# OMAPProc.net
KiCad netlist of a schematic drawn in EAGLE
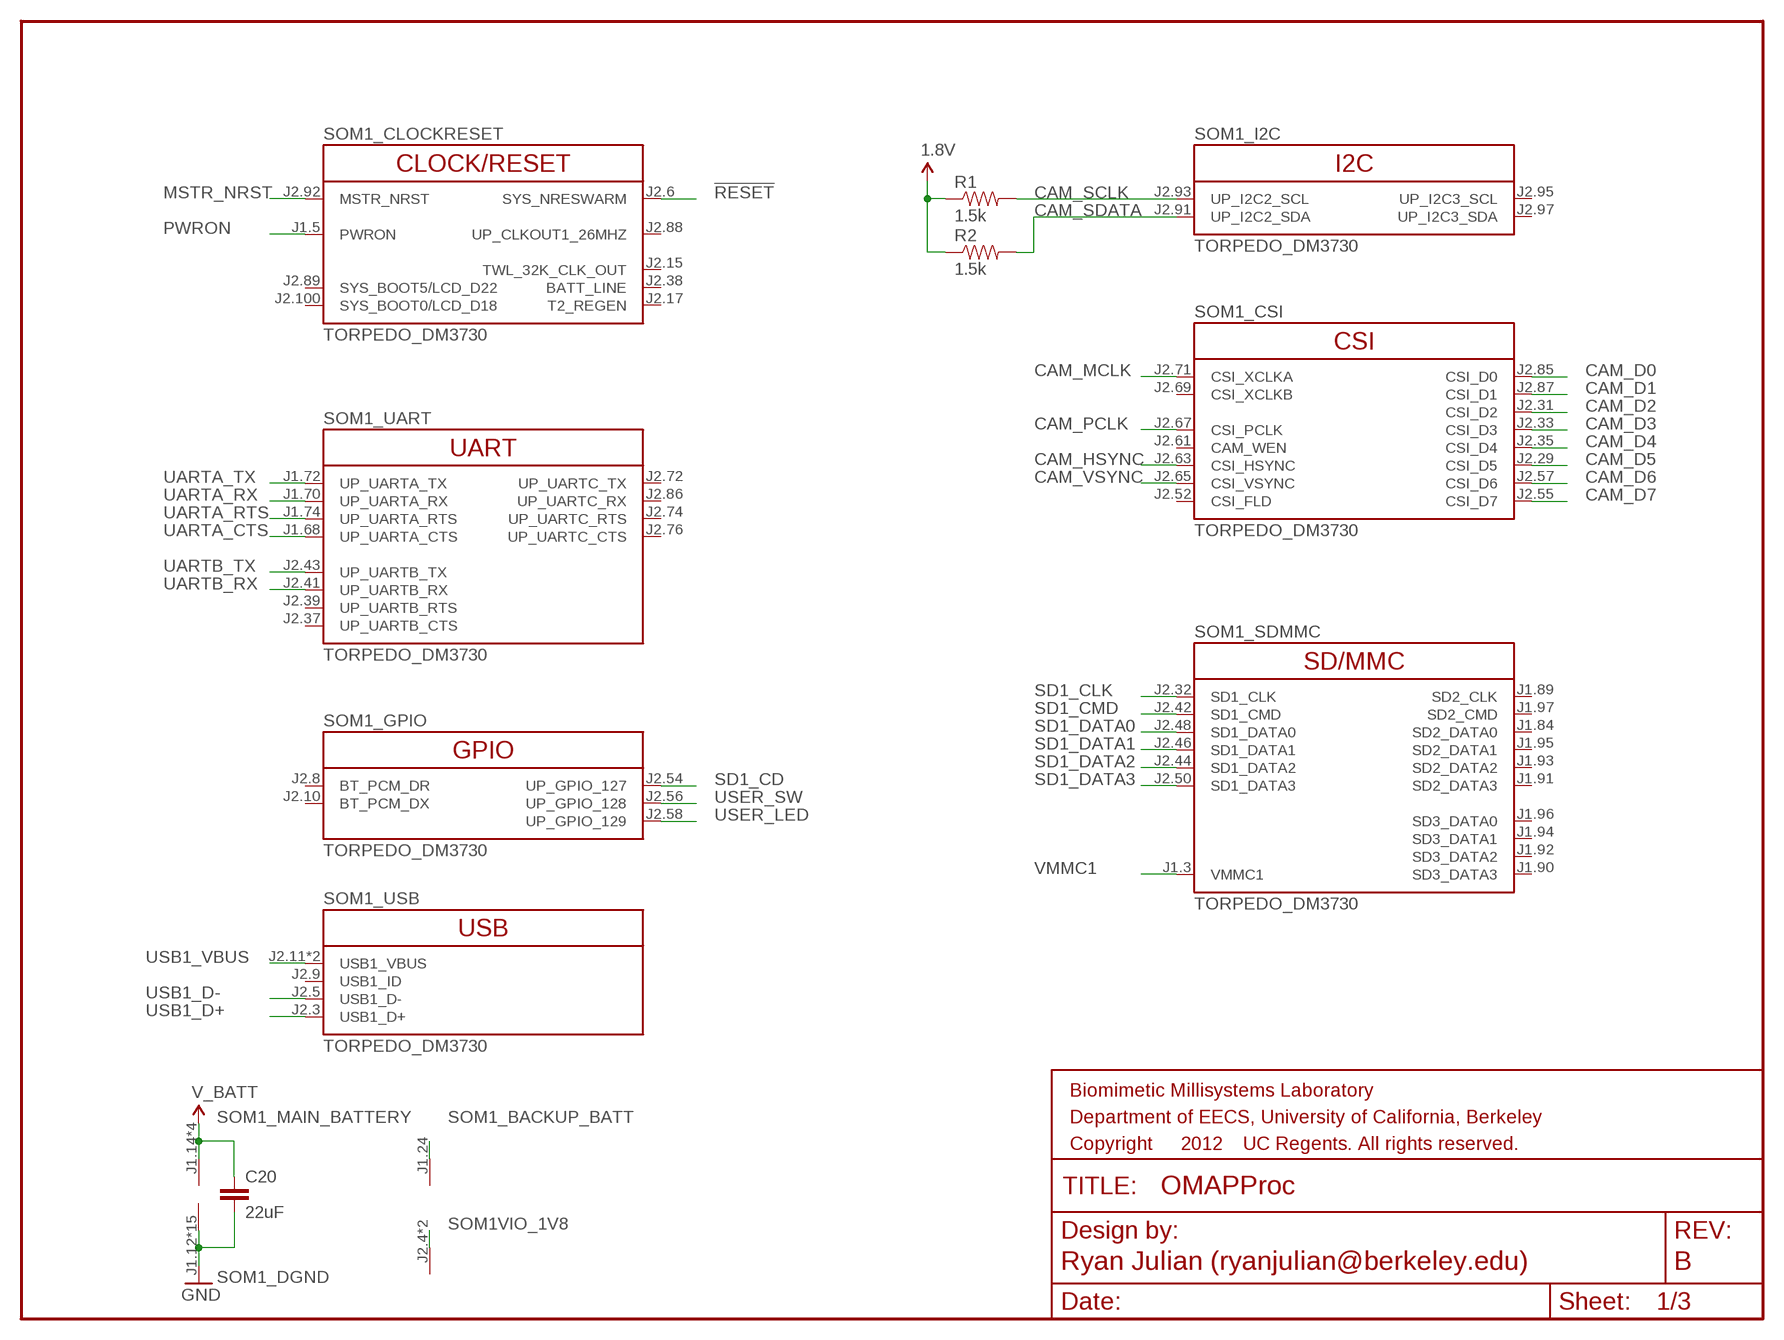
[diagram p0: schematic, sheet 1]
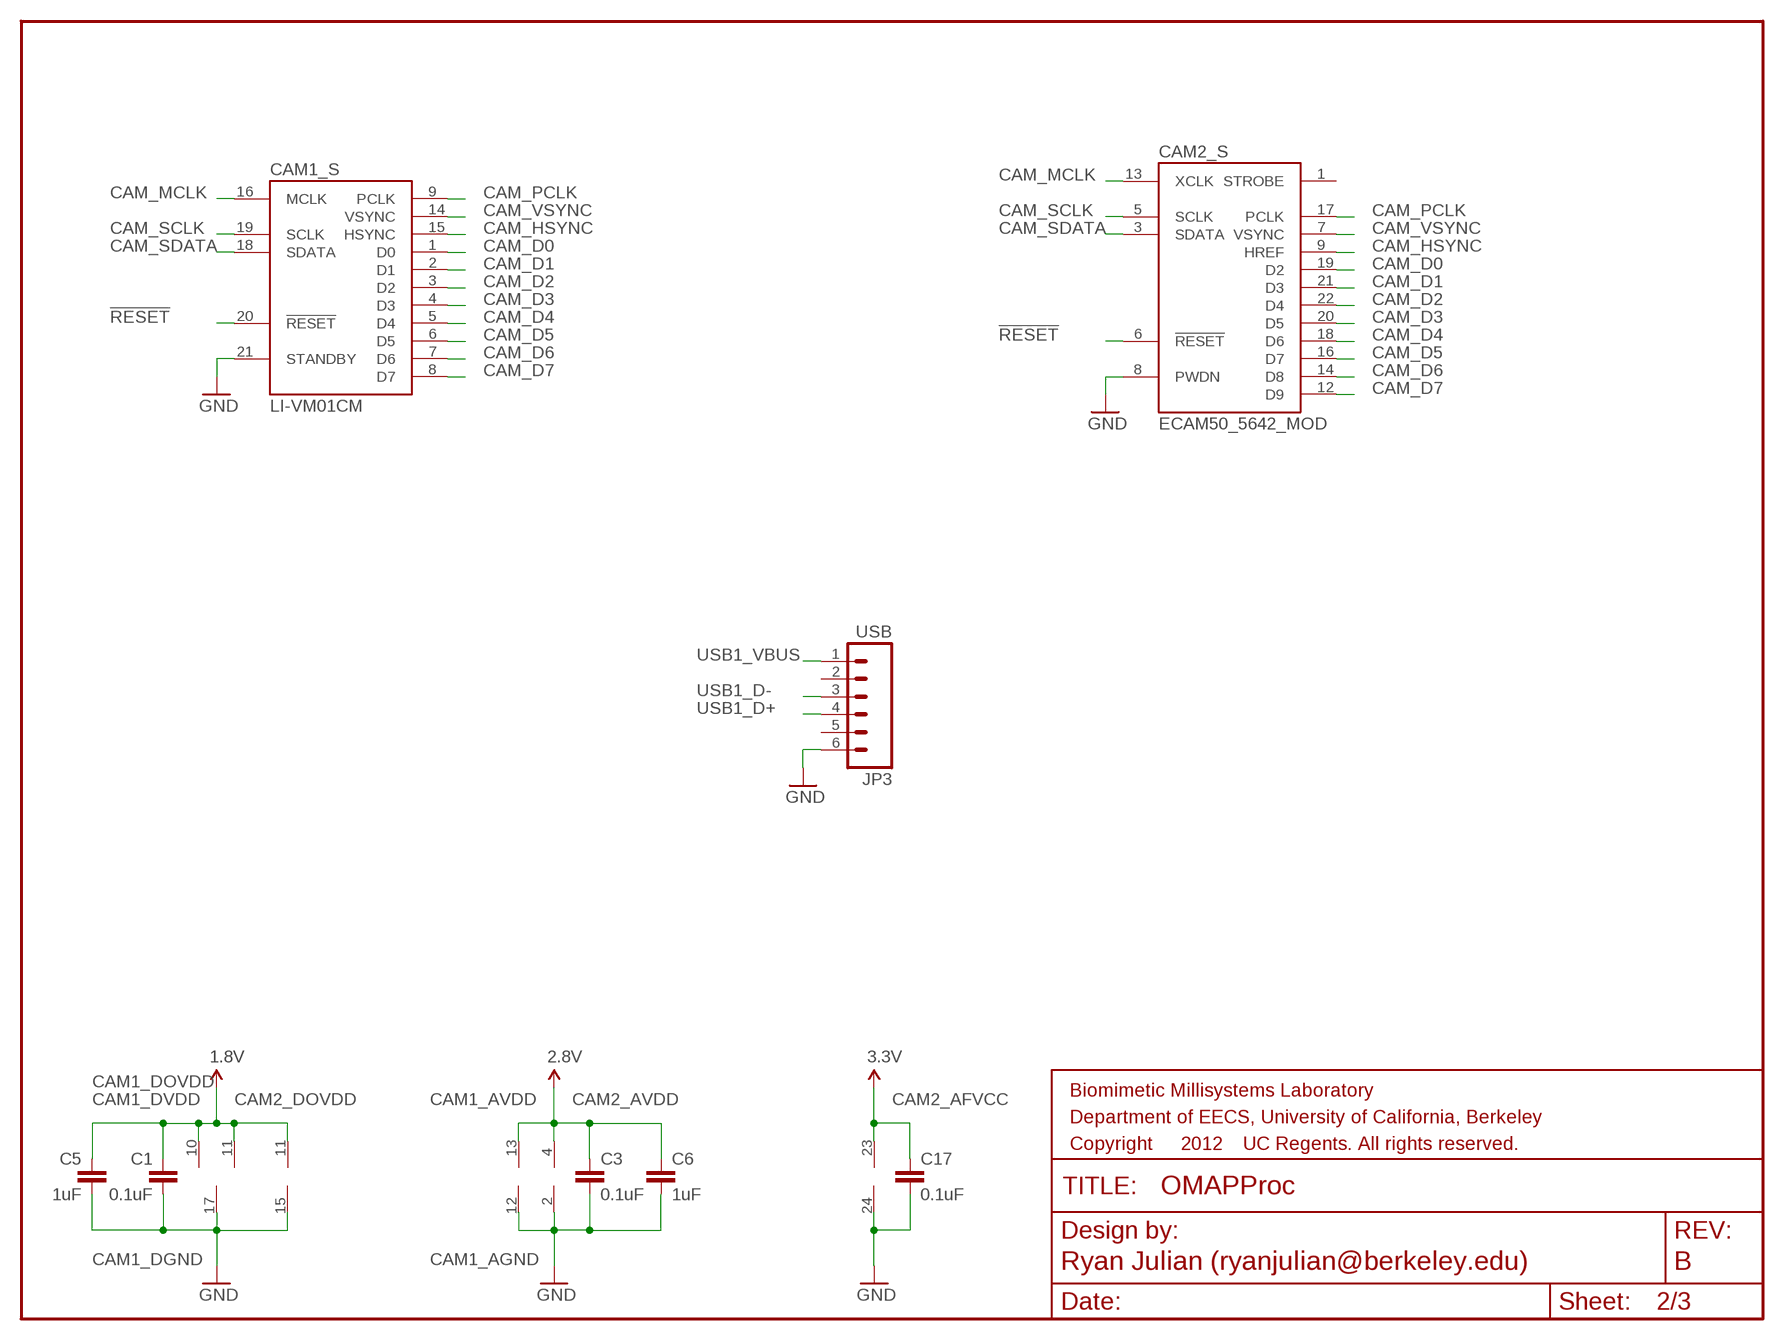
[diagram p1: schematic, sheet 2]
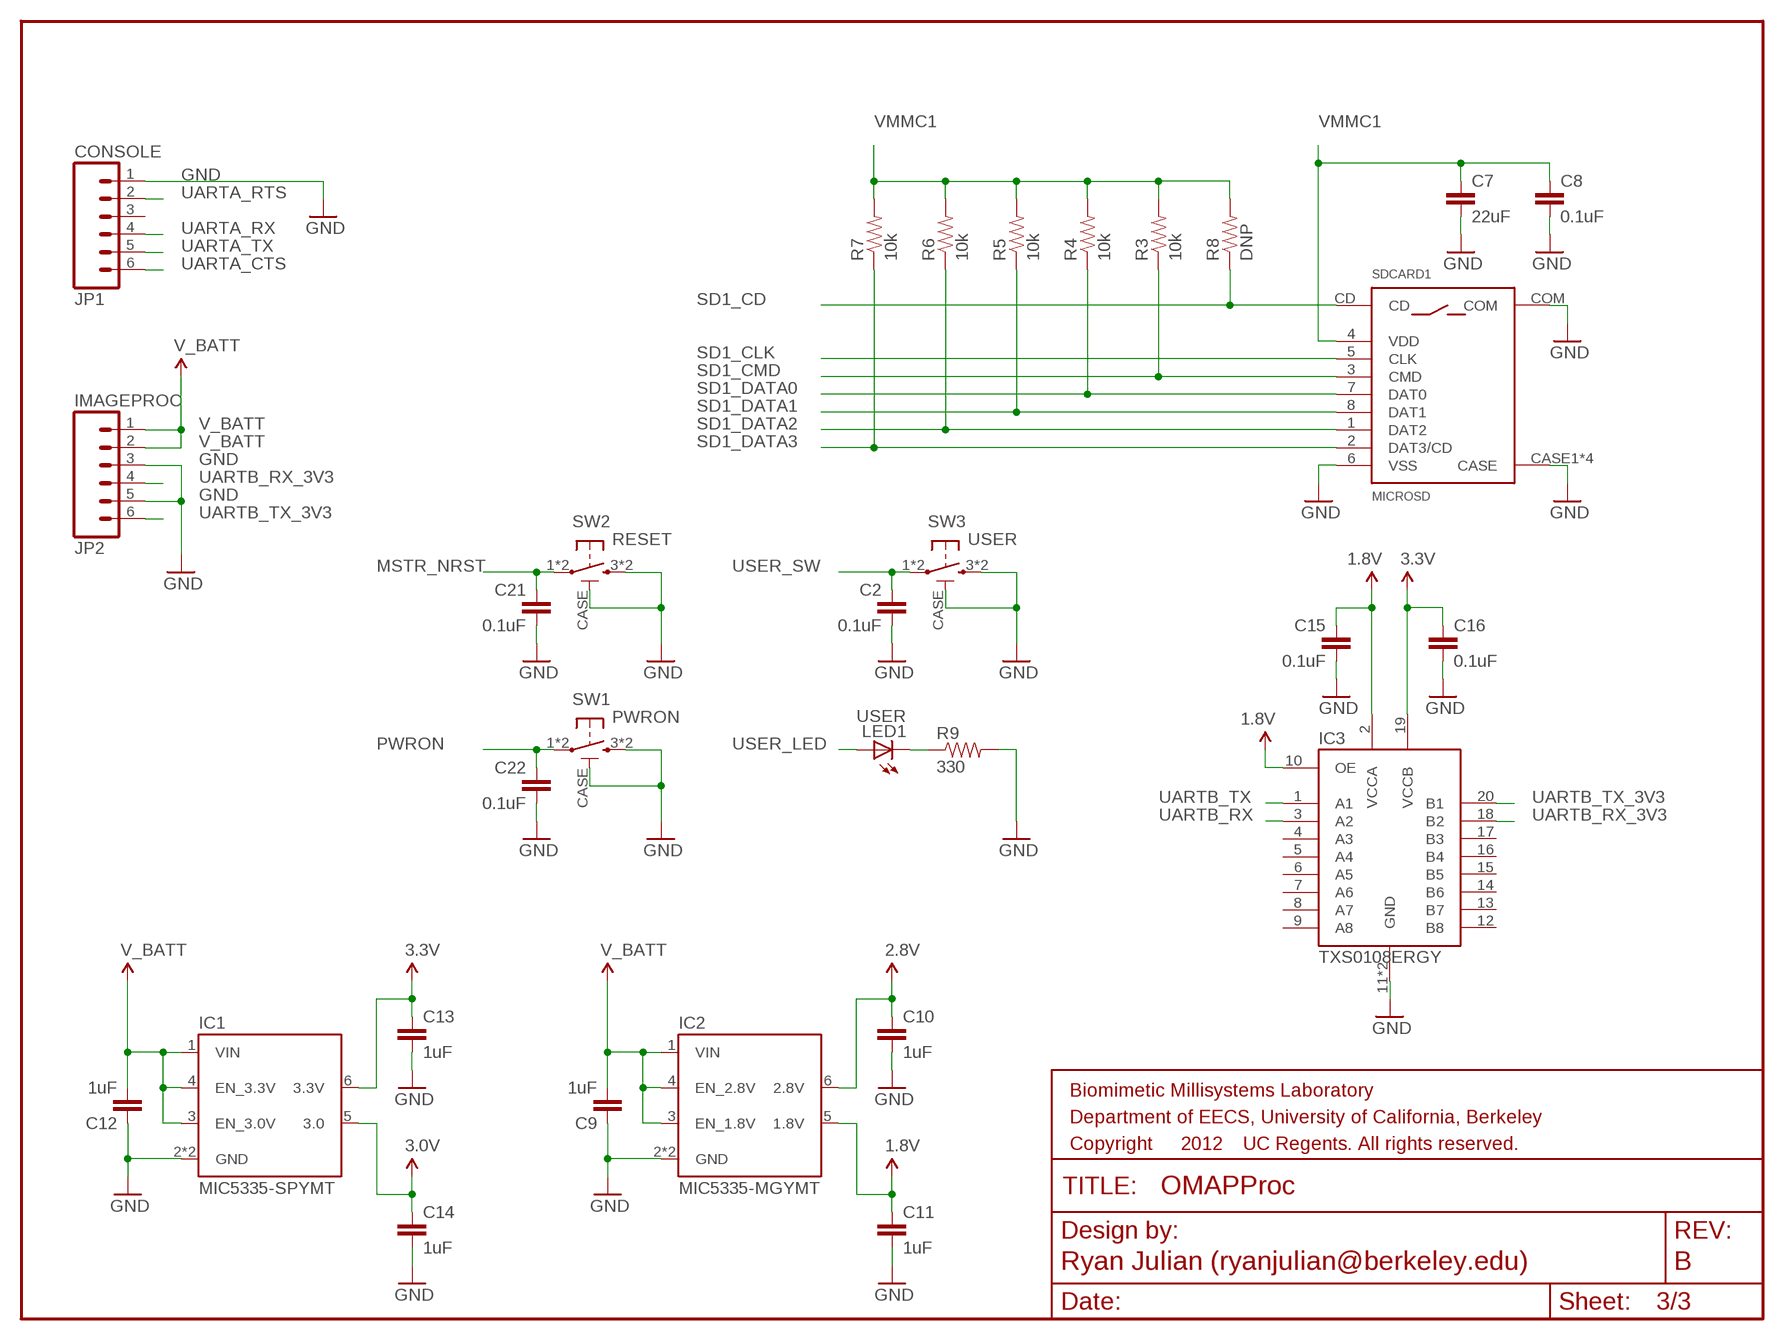
[diagram p2: schematic, sheet 3]

(export (version "E")
  (design (tool "Eeschema 10.0.6"))
  (components
    (comp (ref "C20")
      (value "22uF")
      (footprint "eagle-import:0603-CAP")
      (libsource (lib "eagle-import") (part "CAP0603-CAP"))
    )
    (comp (ref "R1")
      (value "1.5k")
      (footprint "eagle-import:0402-RES")
      (libsource (lib "eagle-import") (part "RESISTOR0402-RES"))
    )
    (comp (ref "R2")
      (value "1.5k")
      (footprint "eagle-import:0402-RES")
      (libsource (lib "eagle-import") (part "RESISTOR0402-RES"))
    )
    (comp (ref "SOM1")
      (value "TORPEDO_DM3730")
      (footprint "eagle-import:TORPEDO_DM3730")
      (libsource (lib "eagle-import") (part "TORPEDO_DM3730"))
    )
    (comp (ref "C1")
      (value "0.1uF")
      (footprint "eagle-import:0402-CAP")
      (libsource (lib "eagle-import") (part "CAP0402-CAP"))
    )
    (comp (ref "C3")
      (value "0.1uF")
      (footprint "eagle-import:0402-CAP")
      (libsource (lib "eagle-import") (part "CAP0402-CAP"))
    )
    (comp (ref "C5")
      (value "1uF")
      (footprint "eagle-import:0402-CAP")
      (libsource (lib "eagle-import") (part "CAP0402-CAP"))
    )
    (comp (ref "C6")
      (value "1uF")
      (footprint "eagle-import:0402-CAP")
      (libsource (lib "eagle-import") (part "CAP0402-CAP"))
    )
    (comp (ref "C17")
      (value "0.1uF")
      (footprint "eagle-import:0402-CAP")
      (libsource (lib "eagle-import") (part "CAP0402-CAP"))
    )
    (comp (ref "CAM1")
      (value "LI-VM01CM")
      (footprint "eagle-import:AXK7L28227G")
      (libsource (lib "eagle-import") (part "LI-VM01CM"))
    )
    (comp (ref "CAM2")
      (value "ECAM50_5642_MOD")
      (footprint "eagle-import:XF2W-2415-1A")
      (libsource (lib "eagle-import") (part "ECAM50_5642_MOD"))
    )
    (comp (ref "JP3")
      (value "USB")
      (footprint "eagle-import:MOLEX_503480-0600")
      (libsource (lib "eagle-import") (part "MOLEX_503480-0600"))
    )
    (comp (ref "C2")
      (value "0.1uF")
      (footprint "eagle-import:0402-CAP")
      (libsource (lib "eagle-import") (part "CAP0402-CAP"))
    )
    (comp (ref "C7")
      (value "22uF")
      (footprint "eagle-import:0603-CAP")
      (libsource (lib "eagle-import") (part "CAP0603-CAP"))
    )
    (comp (ref "C8")
      (value "0.1uF")
      (footprint "eagle-import:0402-CAP")
      (libsource (lib "eagle-import") (part "CAP0402-CAP"))
    )
    (comp (ref "C9")
      (value "1uF")
      (footprint "eagle-import:0402-CAP")
      (libsource (lib "eagle-import") (part "CAP0402-CAP"))
    )
    (comp (ref "C10")
      (value "1uF")
      (footprint "eagle-import:0402-CAP")
      (libsource (lib "eagle-import") (part "CAP0402-CAP"))
    )
    (comp (ref "C11")
      (value "1uF")
      (footprint "eagle-import:0402-CAP")
      (libsource (lib "eagle-import") (part "CAP0402-CAP"))
    )
    (comp (ref "C12")
      (value "1uF")
      (footprint "eagle-import:0402-CAP")
      (libsource (lib "eagle-import") (part "CAP0402-CAP"))
    )
    (comp (ref "C13")
      (value "1uF")
      (footprint "eagle-import:0402-CAP")
      (libsource (lib "eagle-import") (part "CAP0402-CAP"))
    )
    (comp (ref "C14")
      (value "1uF")
      (footprint "eagle-import:0402-CAP")
      (libsource (lib "eagle-import") (part "CAP0402-CAP"))
    )
    (comp (ref "C15")
      (value "0.1uF")
      (footprint "eagle-import:0402-CAP")
      (libsource (lib "eagle-import") (part "CAP0402-CAP"))
    )
    (comp (ref "C16")
      (value "0.1uF")
      (footprint "eagle-import:0402-CAP")
      (libsource (lib "eagle-import") (part "CAP0402-CAP"))
    )
    (comp (ref "C21")
      (value "0.1uF")
      (footprint "eagle-import:0402-CAP")
      (libsource (lib "eagle-import") (part "CAP0402-CAP"))
    )
    (comp (ref "C22")
      (value "0.1uF")
      (footprint "eagle-import:0402-CAP")
      (libsource (lib "eagle-import") (part "CAP0402-CAP"))
    )
    (comp (ref "IC1")
      (value "MIC5335-SPYMT")
      (footprint "eagle-import:MLF-6")
      (libsource (lib "eagle-import") (part "MIC5335-SPYMT"))
    )
    (comp (ref "IC2")
      (value "MIC5335-MGYMT")
      (footprint "eagle-import:MLF-6")
      (libsource (lib "eagle-import") (part "MIC5335-MGYMT"))
    )
    (comp (ref "IC3")
      (value "TXS0108ERGY")
      (footprint "eagle-import:R-PVQFN-N20")
      (libsource (lib "eagle-import") (part "TXS0108ERGY"))
    )
    (comp (ref "JP1")
      (value "CONSOLE")
      (footprint "eagle-import:MOLEX_503480-0600")
      (libsource (lib "eagle-import") (part "MOLEX_503480-0600"))
    )
    (comp (ref "JP2")
      (value "IMAGEPROC")
      (footprint "eagle-import:MOLEX_503480-0600")
      (libsource (lib "eagle-import") (part "MOLEX_503480-0600"))
    )
    (comp (ref "LED1")
      (value "USER")
      (footprint "eagle-import:LED-0603")
      (libsource (lib "eagle-import") (part "LED0603"))
    )
    (comp (ref "R3")
      (value "10k")
      (footprint "eagle-import:0402-RES")
      (libsource (lib "eagle-import") (part "RESISTOR0402-RES"))
    )
    (comp (ref "R4")
      (value "10k")
      (footprint "eagle-import:0402-RES")
      (libsource (lib "eagle-import") (part "RESISTOR0402-RES"))
    )
    (comp (ref "R5")
      (value "10k")
      (footprint "eagle-import:0402-RES")
      (libsource (lib "eagle-import") (part "RESISTOR0402-RES"))
    )
    (comp (ref "R6")
      (value "10k")
      (footprint "eagle-import:0402-RES")
      (libsource (lib "eagle-import") (part "RESISTOR0402-RES"))
    )
    (comp (ref "R7")
      (value "10k")
      (footprint "eagle-import:0402-RES")
      (libsource (lib "eagle-import") (part "RESISTOR0402-RES"))
    )
    (comp (ref "R8")
      (value "DNP")
      (footprint "eagle-import:0402-RES")
      (libsource (lib "eagle-import") (part "RESISTOR0402-RES"))
    )
    (comp (ref "R9")
      (value "330")
      (footprint "eagle-import:0402-RES")
      (libsource (lib "eagle-import") (part "RESISTOR0402-RES"))
    )
    (comp (ref "SDCARD1")
      (value "MICROSD")
      (footprint "eagle-import:AVX_045138008010890+")
      (libsource (lib "eagle-import") (part "MICROSD"))
    )
    (comp (ref "SW1")
      (value "PWRON")
      (footprint "eagle-import:KMR421G")
      (libsource (lib "eagle-import") (part "KMR421GLFS"))
    )
    (comp (ref "SW2")
      (value "RESET")
      (footprint "eagle-import:KMR421G")
      (libsource (lib "eagle-import") (part "KMR421GLFS"))
    )
    (comp (ref "SW3")
      (value "USER")
      (footprint "eagle-import:KMR421G")
      (libsource (lib "eagle-import") (part "KMR421GLFS"))
    )
  )
  (nets
    (net (code "1") (name "1.8V") (class "Default")
      (node (ref "C1") (pin "2") (pinfunction "2_2") (pintype "passive"))
      (node (ref "C11") (pin "1") (pinfunction "1_1") (pintype "passive"))
      (node (ref "C15") (pin "1") (pinfunction "1_1") (pintype "passive"))
      (node (ref "C5") (pin "2") (pinfunction "2_2") (pintype "passive"))
      (node (ref "CAM1") (pin "10") (pinfunction "V+_10") (pintype "power_in"))
      (node (ref "CAM1") (pin "11") (pinfunction "V+_11") (pintype "power_in"))
      (node (ref "CAM2") (pin "11") (pinfunction "V+_11") (pintype "power_in"))
      (node (ref "IC2") (pin "5") (pinfunction "1.8V_5") (pintype "bidirectional"))
      (node (ref "IC3") (pin "10") (pinfunction "OE_10") (pintype "bidirectional"))
      (node (ref "IC3") (pin "2") (pinfunction "VCCA_2") (pintype "bidirectional"))
      (node (ref "R1") (pin "1") (pinfunction "1_1") (pintype "passive"))
      (node (ref "R2") (pin "1") (pinfunction "1_1") (pintype "passive"))
    )
    (net (code "2") (name "2.8V") (class "Default")
      (node (ref "C10") (pin "1") (pinfunction "1_1") (pintype "passive"))
      (node (ref "C3") (pin "1") (pinfunction "1_1") (pintype "passive"))
      (node (ref "C6") (pin "1") (pinfunction "1_1") (pintype "passive"))
      (node (ref "CAM1") (pin "13") (pinfunction "V+_13") (pintype "power_in"))
      (node (ref "CAM2") (pin "4") (pinfunction "V+_4") (pintype "power_in"))
      (node (ref "IC2") (pin "6") (pinfunction "2.8V_6") (pintype "bidirectional"))
    )
    (net (code "3") (name "3.0V") (class "Default")
      (node (ref "C14") (pin "1") (pinfunction "1_1") (pintype "passive"))
      (node (ref "IC1") (pin "5") (pinfunction "3.0_5") (pintype "bidirectional"))
    )
    (net (code "4") (name "3.3V") (class "Default")
      (node (ref "C13") (pin "1") (pinfunction "1_1") (pintype "passive"))
      (node (ref "C16") (pin "1") (pinfunction "1_1") (pintype "passive"))
      (node (ref "C17") (pin "1") (pinfunction "1_1") (pintype "passive"))
      (node (ref "CAM2") (pin "23") (pinfunction "V+_23") (pintype "power_in"))
      (node (ref "IC1") (pin "6") (pinfunction "3.3V_6") (pintype "bidirectional"))
      (node (ref "IC3") (pin "19") (pinfunction "VCCB_19") (pintype "bidirectional"))
    )
    (net (code "5") (name "CAM_D0") (class "Default")
      (node (ref "CAM1") (pin "1") (pinfunction "D0_1") (pintype "output"))
      (node (ref "CAM2") (pin "19") (pinfunction "D2_19") (pintype "output"))
      (node (ref "SOM1") (pin "J2.85") (pinfunction "CSI_D0_J2.85") (pintype "bidirectional"))
    )
    (net (code "6") (name "CAM_D1") (class "Default")
      (node (ref "CAM1") (pin "2") (pinfunction "D1_2") (pintype "output"))
      (node (ref "CAM2") (pin "21") (pinfunction "D3_21") (pintype "output"))
      (node (ref "SOM1") (pin "J2.87") (pinfunction "CSI_D1_J2.87") (pintype "bidirectional"))
    )
    (net (code "7") (name "CAM_D2") (class "Default")
      (node (ref "CAM1") (pin "3") (pinfunction "D2_3") (pintype "output"))
      (node (ref "CAM2") (pin "22") (pinfunction "D4_22") (pintype "output"))
      (node (ref "SOM1") (pin "J2.31") (pinfunction "CSI_D2_J2.31") (pintype "bidirectional"))
    )
    (net (code "8") (name "CAM_D3") (class "Default")
      (node (ref "CAM1") (pin "4") (pinfunction "D3_4") (pintype "output"))
      (node (ref "CAM2") (pin "20") (pinfunction "D5_20") (pintype "output"))
      (node (ref "SOM1") (pin "J2.33") (pinfunction "CSI_D3_J2.33") (pintype "bidirectional"))
    )
    (net (code "9") (name "CAM_D4") (class "Default")
      (node (ref "CAM1") (pin "5") (pinfunction "D4_5") (pintype "output"))
      (node (ref "CAM2") (pin "18") (pinfunction "D6_18") (pintype "output"))
      (node (ref "SOM1") (pin "J2.35") (pinfunction "CSI_D4_J2.35") (pintype "bidirectional"))
    )
    (net (code "10") (name "CAM_D5") (class "Default")
      (node (ref "CAM1") (pin "6") (pinfunction "D5_6") (pintype "output"))
      (node (ref "CAM2") (pin "16") (pinfunction "D7_16") (pintype "output"))
      (node (ref "SOM1") (pin "J2.29") (pinfunction "CSI_D5_J2.29") (pintype "bidirectional"))
    )
    (net (code "11") (name "CAM_D6") (class "Default")
      (node (ref "CAM1") (pin "7") (pinfunction "D6_7") (pintype "output"))
      (node (ref "CAM2") (pin "14") (pinfunction "D8_14") (pintype "output"))
      (node (ref "SOM1") (pin "J2.57") (pinfunction "CSI_D6_J2.57") (pintype "bidirectional"))
    )
    (net (code "12") (name "CAM_D7") (class "Default")
      (node (ref "CAM1") (pin "8") (pinfunction "D7_8") (pintype "output"))
      (node (ref "CAM2") (pin "12") (pinfunction "D9_12") (pintype "output"))
      (node (ref "SOM1") (pin "J2.55") (pinfunction "CSI_D7_J2.55") (pintype "bidirectional"))
    )
    (net (code "13") (name "CAM_HSYNC") (class "Default")
      (node (ref "CAM1") (pin "15") (pinfunction "HSYNC_15") (pintype "input"))
      (node (ref "CAM2") (pin "9") (pinfunction "HREF_9") (pintype "input"))
      (node (ref "SOM1") (pin "J2.63") (pinfunction "CSI_HSYNC_J2.63") (pintype "bidirectional"))
    )
    (net (code "14") (name "CAM_MCLK") (class "Default")
      (node (ref "CAM1") (pin "16") (pinfunction "MCLK_16") (pintype "input"))
      (node (ref "CAM2") (pin "13") (pinfunction "XCLK_13") (pintype "input"))
      (node (ref "SOM1") (pin "J2.71") (pinfunction "CSI_XCLKA_J2.71") (pintype "bidirectional"))
    )
    (net (code "15") (name "CAM_PCLK") (class "Default")
      (node (ref "CAM1") (pin "9") (pinfunction "PCLK_9") (pintype "output"))
      (node (ref "CAM2") (pin "17") (pinfunction "PCLK_17") (pintype "output"))
      (node (ref "SOM1") (pin "J2.67") (pinfunction "CSI_PCLK_J2.67") (pintype "bidirectional"))
    )
    (net (code "16") (name "CAM_SCLK") (class "Default")
      (node (ref "CAM1") (pin "19") (pinfunction "SCLK_19") (pintype "input"))
      (node (ref "CAM2") (pin "5") (pinfunction "SCLK_5") (pintype "input"))
      (node (ref "R1") (pin "2") (pinfunction "2_2") (pintype "passive"))
      (node (ref "SOM1") (pin "J2.93") (pinfunction "UP_I2C2_SCL_J2.93") (pintype "bidirectional"))
    )
    (net (code "17") (name "CAM_SDATA") (class "Default")
      (node (ref "CAM1") (pin "18") (pinfunction "SDATA_18") (pintype "bidirectional"))
      (node (ref "CAM2") (pin "3") (pinfunction "SDATA_3") (pintype "bidirectional"))
      (node (ref "R2") (pin "2") (pinfunction "2_2") (pintype "passive"))
      (node (ref "SOM1") (pin "J2.91") (pinfunction "UP_I2C2_SDA_J2.91") (pintype "bidirectional"))
    )
    (net (code "18") (name "CAM_VSYNC") (class "Default")
      (node (ref "CAM1") (pin "14") (pinfunction "VSYNC_14") (pintype "input"))
      (node (ref "CAM2") (pin "7") (pinfunction "VSYNC_7") (pintype "input"))
      (node (ref "SOM1") (pin "J2.65") (pinfunction "CSI_VSYNC_J2.65") (pintype "bidirectional"))
    )
    (net (code "19") (name "GND") (class "Default")
      (node (ref "C1") (pin "1") (pinfunction "1_1") (pintype "passive"))
      (node (ref "C10") (pin "2") (pinfunction "2_2") (pintype "passive"))
      (node (ref "C11") (pin "2") (pinfunction "2_2") (pintype "passive"))
      (node (ref "C12") (pin "1") (pinfunction "1_1") (pintype "passive"))
      (node (ref "C13") (pin "2") (pinfunction "2_2") (pintype "passive"))
      (node (ref "C14") (pin "2") (pinfunction "2_2") (pintype "passive"))
      (node (ref "C15") (pin "2") (pinfunction "2_2") (pintype "passive"))
      (node (ref "C16") (pin "2") (pinfunction "2_2") (pintype "passive"))
      (node (ref "C17") (pin "2") (pinfunction "2_2") (pintype "passive"))
      (node (ref "C2") (pin "2") (pinfunction "2_2") (pintype "passive"))
      (node (ref "C20") (pin "2") (pinfunction "2_2") (pintype "passive"))
      (node (ref "C21") (pin "2") (pinfunction "2_2") (pintype "passive"))
      (node (ref "C22") (pin "2") (pinfunction "2_2") (pintype "passive"))
      (node (ref "C3") (pin "2") (pinfunction "2_2") (pintype "passive"))
      (node (ref "C5") (pin "1") (pinfunction "1_1") (pintype "passive"))
      (node (ref "C6") (pin "2") (pinfunction "2_2") (pintype "passive"))
      (node (ref "C7") (pin "2") (pinfunction "2_2") (pintype "passive"))
      (node (ref "C8") (pin "2") (pinfunction "2_2") (pintype "passive"))
      (node (ref "C9") (pin "1") (pinfunction "1_1") (pintype "passive"))
      (node (ref "CAM1") (pin "12") (pinfunction "V-_12") (pintype "power_in"))
      (node (ref "CAM1") (pin "17") (pinfunction "V-_17") (pintype "power_in"))
      (node (ref "CAM1") (pin "21") (pinfunction "STANDBY_21") (pintype "input"))
      (node (ref "CAM2") (pin "15") (pinfunction "V-_15") (pintype "power_in"))
      (node (ref "CAM2") (pin "2") (pinfunction "V-_2") (pintype "power_in"))
      (node (ref "CAM2") (pin "24") (pinfunction "V-_24") (pintype "power_in"))
      (node (ref "CAM2") (pin "8") (pinfunction "PWDN_8") (pintype "input"))
      (node (ref "IC1") (pin "2") (pinfunction "GND_2") (pintype "bidirectional"))
      (node (ref "IC1") (pin "EPAD") (pinfunction "GND_EPAD") (pintype "bidirectional"))
      (node (ref "IC2") (pin "2") (pinfunction "GND_2") (pintype "bidirectional"))
      (node (ref "IC2") (pin "EPAD") (pinfunction "GND_EPAD") (pintype "bidirectional"))
      (node (ref "IC3") (pin "11") (pinfunction "GND_11") (pintype "bidirectional"))
      (node (ref "IC3") (pin "EPAD") (pinfunction "GND_EPAD") (pintype "bidirectional"))
      (node (ref "JP1") (pin "1") (pinfunction "1_1") (pintype "passive"))
      (node (ref "JP2") (pin "3") (pinfunction "3_3") (pintype "passive"))
      (node (ref "JP2") (pin "5") (pinfunction "5_5") (pintype "passive"))
      (node (ref "JP3") (pin "6") (pinfunction "6_6") (pintype "passive"))
      (node (ref "R9") (pin "2") (pinfunction "2_2") (pintype "passive"))
      (node (ref "SDCARD1") (pin "6") (pinfunction "VSS_6") (pintype "bidirectional"))
      (node (ref "SDCARD1") (pin "CASE1") (pinfunction "CASE_CASE1") (pintype "bidirectional"))
      (node (ref "SDCARD1") (pin "CASE2") (pinfunction "CASE_CASE2") (pintype "bidirectional"))
      (node (ref "SDCARD1") (pin "CASE3") (pinfunction "CASE_CASE3") (pintype "bidirectional"))
      (node (ref "SDCARD1") (pin "CASE4") (pinfunction "CASE_CASE4") (pintype "bidirectional"))
      (node (ref "SDCARD1") (pin "COM") (pinfunction "COM_COM") (pintype "bidirectional"))
      (node (ref "SOM1") (pin "J1.100") (pinfunction "V-_J1.100") (pintype "power_in"))
      (node (ref "SOM1") (pin "J1.12") (pinfunction "V-_J1.12") (pintype "power_in"))
      (node (ref "SOM1") (pin "J1.17") (pinfunction "V-_J1.17") (pintype "power_in"))
      (node (ref "SOM1") (pin "J1.22") (pinfunction "V-_J1.22") (pintype "power_in"))
      (node (ref "SOM1") (pin "J1.27") (pinfunction "V-_J1.27") (pintype "power_in"))
      (node (ref "SOM1") (pin "J1.61") (pinfunction "V-_J1.61") (pintype "power_in"))
      (node (ref "SOM1") (pin "J1.85") (pinfunction "V-_J1.85") (pintype "power_in"))
      (node (ref "SOM1") (pin "J2.1") (pinfunction "V-_J2.1") (pintype "power_in"))
      (node (ref "SOM1") (pin "J2.2") (pinfunction "V-_J2.2") (pintype "power_in"))
      (node (ref "SOM1") (pin "J2.27") (pinfunction "V-_J2.27") (pintype "power_in"))
      (node (ref "SOM1") (pin "J2.30") (pinfunction "V-_J2.30") (pintype "power_in"))
      (node (ref "SOM1") (pin "J2.59") (pinfunction "V-_J2.59") (pintype "power_in"))
      (node (ref "SOM1") (pin "J2.62") (pinfunction "V-_J2.62") (pintype "power_in"))
      (node (ref "SOM1") (pin "J2.90") (pinfunction "V-_J2.90") (pintype "power_in"))
      (node (ref "SOM1") (pin "J2.99") (pinfunction "V-_J2.99") (pintype "power_in"))
      (node (ref "SW1") (pin "3") (pinfunction "S_3") (pintype "passive"))
      (node (ref "SW1") (pin "4") (pinfunction "S_4") (pintype "passive"))
      (node (ref "SW1") (pin "CASE") (pinfunction "CASE_CASE") (pintype "passive"))
      (node (ref "SW2") (pin "3") (pinfunction "S_3") (pintype "passive"))
      (node (ref "SW2") (pin "4") (pinfunction "S_4") (pintype "passive"))
      (node (ref "SW2") (pin "CASE") (pinfunction "CASE_CASE") (pintype "passive"))
      (node (ref "SW3") (pin "3") (pinfunction "S_3") (pintype "passive"))
      (node (ref "SW3") (pin "4") (pinfunction "S_4") (pintype "passive"))
      (node (ref "SW3") (pin "CASE") (pinfunction "CASE_CASE") (pintype "passive"))
    )
    (net (code "20") (name "MSTR_NRST") (class "Default")
      (node (ref "C21") (pin "1") (pinfunction "1_1") (pintype "passive"))
      (node (ref "SOM1") (pin "J2.92") (pinfunction "MSTR_NRST_J2.92") (pintype "bidirectional"))
      (node (ref "SW2") (pin "1") (pinfunction "P_1") (pintype "passive"))
      (node (ref "SW2") (pin "2") (pinfunction "P_2") (pintype "passive"))
    )
    (net (code "21") (name "Net-(LED1-PadC)") (class "Default")
      (node (ref "LED1") (pin "C") (pinfunction "C_C") (pintype "passive"))
      (node (ref "R9") (pin "1") (pinfunction "1_1") (pintype "passive"))
    )
    (net (code "22") (name "Net-(SOM1A-V+-PadJ2.4)") (class "Default")
      (node (ref "SOM1") (pin "J2.4") (pinfunction "V+_J2.4") (pintype "power_in"))
      (node (ref "SOM1") (pin "J2.7") (pinfunction "V+_J2.7") (pintype "power_in"))
    )
    (net (code "23") (name "PWRON") (class "Default")
      (node (ref "C22") (pin "1") (pinfunction "1_1") (pintype "passive"))
      (node (ref "SOM1") (pin "J1.5") (pinfunction "PWRON_J1.5") (pintype "bidirectional"))
      (node (ref "SW1") (pin "1") (pinfunction "P_1") (pintype "passive"))
      (node (ref "SW1") (pin "2") (pinfunction "P_2") (pintype "passive"))
    )
    (net (code "24") (name "SD1_CD") (class "Default")
      (node (ref "R8") (pin "1") (pinfunction "1_1") (pintype "passive"))
      (node (ref "SDCARD1") (pin "CD") (pinfunction "CD_CD") (pintype "bidirectional"))
      (node (ref "SOM1") (pin "J2.54") (pinfunction "UP_GPIO_127_J2.54") (pintype "bidirectional"))
    )
    (net (code "25") (name "SD1_CLK") (class "Default")
      (node (ref "SDCARD1") (pin "5") (pinfunction "CLK_5") (pintype "bidirectional"))
      (node (ref "SOM1") (pin "J2.32") (pinfunction "SD1_CLK_J2.32") (pintype "bidirectional"))
    )
    (net (code "26") (name "SD1_CMD") (class "Default")
      (node (ref "R3") (pin "1") (pinfunction "1_1") (pintype "passive"))
      (node (ref "SDCARD1") (pin "3") (pinfunction "CMD_3") (pintype "bidirectional"))
      (node (ref "SOM1") (pin "J2.42") (pinfunction "SD1_CMD_J2.42") (pintype "bidirectional"))
    )
    (net (code "27") (name "SD1_DATA0") (class "Default")
      (node (ref "R4") (pin "1") (pinfunction "1_1") (pintype "passive"))
      (node (ref "SDCARD1") (pin "7") (pinfunction "DAT0_7") (pintype "bidirectional"))
      (node (ref "SOM1") (pin "J2.48") (pinfunction "SD1_DATA0_J2.48") (pintype "bidirectional"))
    )
    (net (code "28") (name "SD1_DATA1") (class "Default")
      (node (ref "R5") (pin "1") (pinfunction "1_1") (pintype "passive"))
      (node (ref "SDCARD1") (pin "8") (pinfunction "DAT1_8") (pintype "bidirectional"))
      (node (ref "SOM1") (pin "J2.46") (pinfunction "SD1_DATA1_J2.46") (pintype "bidirectional"))
    )
    (net (code "29") (name "SD1_DATA2") (class "Default")
      (node (ref "R6") (pin "1") (pinfunction "1_1") (pintype "passive"))
      (node (ref "SDCARD1") (pin "1") (pinfunction "DAT2_1") (pintype "bidirectional"))
      (node (ref "SOM1") (pin "J2.44") (pinfunction "SD1_DATA2_J2.44") (pintype "bidirectional"))
    )
    (net (code "30") (name "SD1_DATA3") (class "Default")
      (node (ref "R7") (pin "1") (pinfunction "1_1") (pintype "passive"))
      (node (ref "SDCARD1") (pin "2") (pinfunction "DAT3/CD_2") (pintype "bidirectional"))
      (node (ref "SOM1") (pin "J2.50") (pinfunction "SD1_DATA3_J2.50") (pintype "bidirectional"))
    )
    (net (code "31") (name "UARTA_CTS") (class "Default")
      (node (ref "JP1") (pin "6") (pinfunction "6_6") (pintype "passive"))
      (node (ref "SOM1") (pin "J1.68") (pinfunction "UP_UARTA_CTS_J1.68") (pintype "bidirectional"))
    )
    (net (code "32") (name "UARTA_RTS") (class "Default")
      (node (ref "JP1") (pin "2") (pinfunction "2_2") (pintype "passive"))
      (node (ref "SOM1") (pin "J1.74") (pinfunction "UP_UARTA_RTS_J1.74") (pintype "bidirectional"))
    )
    (net (code "33") (name "UARTA_RX") (class "Default")
      (node (ref "JP1") (pin "4") (pinfunction "4_4") (pintype "passive"))
      (node (ref "SOM1") (pin "J1.70") (pinfunction "UP_UARTA_RX_J1.70") (pintype "bidirectional"))
    )
    (net (code "34") (name "UARTA_TX") (class "Default")
      (node (ref "JP1") (pin "5") (pinfunction "5_5") (pintype "passive"))
      (node (ref "SOM1") (pin "J1.72") (pinfunction "UP_UARTA_TX_J1.72") (pintype "bidirectional"))
    )
    (net (code "35") (name "UARTB_RX") (class "Default")
      (node (ref "IC3") (pin "3") (pinfunction "A2_3") (pintype "bidirectional"))
      (node (ref "SOM1") (pin "J2.41") (pinfunction "UP_UARTB_RX_J2.41") (pintype "bidirectional"))
    )
    (net (code "36") (name "UARTB_RX_3V3") (class "Default")
      (node (ref "IC3") (pin "18") (pinfunction "B2_18") (pintype "bidirectional"))
      (node (ref "JP2") (pin "4") (pinfunction "4_4") (pintype "passive"))
    )
    (net (code "37") (name "UARTB_TX") (class "Default")
      (node (ref "IC3") (pin "1") (pinfunction "A1_1") (pintype "bidirectional"))
      (node (ref "SOM1") (pin "J2.43") (pinfunction "UP_UARTB_TX_J2.43") (pintype "bidirectional"))
    )
    (net (code "38") (name "UARTB_TX_3V3") (class "Default")
      (node (ref "IC3") (pin "20") (pinfunction "B1_20") (pintype "bidirectional"))
      (node (ref "JP2") (pin "6") (pinfunction "6_6") (pintype "passive"))
    )
    (net (code "39") (name "USB1_D+") (class "Default")
      (node (ref "JP3") (pin "4") (pinfunction "4_4") (pintype "passive"))
      (node (ref "SOM1") (pin "J2.3") (pinfunction "USB1_D+_J2.3") (pintype "bidirectional"))
    )
    (net (code "40") (name "USB1_D-") (class "Default")
      (node (ref "JP3") (pin "3") (pinfunction "3_3") (pintype "passive"))
      (node (ref "SOM1") (pin "J2.5") (pinfunction "USB1_D-_J2.5") (pintype "bidirectional"))
    )
    (net (code "41") (name "USB1_VBUS") (class "Default")
      (node (ref "JP3") (pin "1") (pinfunction "1_1") (pintype "passive"))
      (node (ref "SOM1") (pin "J2.11") (pinfunction "USB1_VBUS_J2.11") (pintype "bidirectional"))
      (node (ref "SOM1") (pin "J2.13") (pinfunction "USB1_VBUS_J2.13") (pintype "bidirectional"))
    )
    (net (code "42") (name "USER_LED") (class "Default")
      (node (ref "LED1") (pin "A") (pinfunction "A_A") (pintype "passive"))
      (node (ref "SOM1") (pin "J2.58") (pinfunction "UP_GPIO_129_J2.58") (pintype "bidirectional"))
    )
    (net (code "43") (name "USER_SW") (class "Default")
      (node (ref "C2") (pin "1") (pinfunction "1_1") (pintype "passive"))
      (node (ref "SOM1") (pin "J2.56") (pinfunction "UP_GPIO_128_J2.56") (pintype "bidirectional"))
      (node (ref "SW3") (pin "1") (pinfunction "P_1") (pintype "passive"))
      (node (ref "SW3") (pin "2") (pinfunction "P_2") (pintype "passive"))
    )
    (net (code "44") (name "VMMC1") (class "Default")
      (node (ref "C7") (pin "1") (pinfunction "1_1") (pintype "passive"))
      (node (ref "C8") (pin "1") (pinfunction "1_1") (pintype "passive"))
      (node (ref "R3") (pin "2") (pinfunction "2_2") (pintype "passive"))
      (node (ref "R4") (pin "2") (pinfunction "2_2") (pintype "passive"))
      (node (ref "R5") (pin "2") (pinfunction "2_2") (pintype "passive"))
      (node (ref "R6") (pin "2") (pinfunction "2_2") (pintype "passive"))
      (node (ref "R7") (pin "2") (pinfunction "2_2") (pintype "passive"))
      (node (ref "R8") (pin "2") (pinfunction "2_2") (pintype "passive"))
      (node (ref "SDCARD1") (pin "4") (pinfunction "VDD_4") (pintype "bidirectional"))
      (node (ref "SOM1") (pin "J1.3") (pinfunction "VMMC1_J1.3") (pintype "bidirectional"))
    )
    (net (code "45") (name "V_BATT") (class "Default")
      (node (ref "C12") (pin "2") (pinfunction "2_2") (pintype "passive"))
      (node (ref "C20") (pin "1") (pinfunction "1_1") (pintype "passive"))
      (node (ref "C9") (pin "2") (pinfunction "2_2") (pintype "passive"))
      (node (ref "IC1") (pin "1") (pinfunction "VIN_1") (pintype "bidirectional"))
      (node (ref "IC1") (pin "3") (pinfunction "EN_3.0V_3") (pintype "bidirectional"))
      (node (ref "IC1") (pin "4") (pinfunction "EN_3.3V_4") (pintype "bidirectional"))
      (node (ref "IC2") (pin "1") (pinfunction "VIN_1") (pintype "bidirectional"))
      (node (ref "IC2") (pin "3") (pinfunction "EN_1.8V_3") (pintype "bidirectional"))
      (node (ref "IC2") (pin "4") (pinfunction "EN_2.8V_4") (pintype "bidirectional"))
      (node (ref "JP2") (pin "1") (pinfunction "1_1") (pintype "passive"))
      (node (ref "JP2") (pin "2") (pinfunction "2_2") (pintype "passive"))
      (node (ref "SOM1") (pin "J1.14") (pinfunction "V+_J1.14") (pintype "power_in"))
      (node (ref "SOM1") (pin "J1.16") (pinfunction "V+_J1.16") (pintype "power_in"))
      (node (ref "SOM1") (pin "J1.18") (pinfunction "V+_J1.18") (pintype "power_in"))
      (node (ref "SOM1") (pin "J1.20") (pinfunction "V+_J1.20") (pintype "power_in"))
    )
    (net (code "46") (name "unconnected-(CAM2D-STROBE-Pad1)") (class "Default")
      (node (ref "CAM2") (pin "1") (pinfunction "STROBE_1") (pintype "bidirectional"))
    )
    (net (code "47") (name "unconnected-(IC3-A3-Pad4)") (class "Default")
      (node (ref "IC3") (pin "4") (pinfunction "A3_4") (pintype "bidirectional"))
    )
    (net (code "48") (name "unconnected-(IC3-A4-Pad5)") (class "Default")
      (node (ref "IC3") (pin "5") (pinfunction "A4_5") (pintype "bidirectional"))
    )
    (net (code "49") (name "unconnected-(IC3-A5-Pad6)") (class "Default")
      (node (ref "IC3") (pin "6") (pinfunction "A5_6") (pintype "bidirectional"))
    )
    (net (code "50") (name "unconnected-(IC3-A6-Pad7)") (class "Default")
      (node (ref "IC3") (pin "7") (pinfunction "A6_7") (pintype "bidirectional"))
    )
    (net (code "51") (name "unconnected-(IC3-A7-Pad8)") (class "Default")
      (node (ref "IC3") (pin "8") (pinfunction "A7_8") (pintype "bidirectional"))
    )
    (net (code "52") (name "unconnected-(IC3-A8-Pad9)") (class "Default")
      (node (ref "IC3") (pin "9") (pinfunction "A8_9") (pintype "bidirectional"))
    )
    (net (code "53") (name "unconnected-(IC3-B3-Pad17)") (class "Default")
      (node (ref "IC3") (pin "17") (pinfunction "B3_17") (pintype "bidirectional"))
    )
    (net (code "54") (name "unconnected-(IC3-B4-Pad16)") (class "Default")
      (node (ref "IC3") (pin "16") (pinfunction "B4_16") (pintype "bidirectional"))
    )
    (net (code "55") (name "unconnected-(IC3-B5-Pad15)") (class "Default")
      (node (ref "IC3") (pin "15") (pinfunction "B5_15") (pintype "bidirectional"))
    )
    (net (code "56") (name "unconnected-(IC3-B6-Pad14)") (class "Default")
      (node (ref "IC3") (pin "14") (pinfunction "B6_14") (pintype "bidirectional"))
    )
    (net (code "57") (name "unconnected-(IC3-B7-Pad13)") (class "Default")
      (node (ref "IC3") (pin "13") (pinfunction "B7_13") (pintype "bidirectional"))
    )
    (net (code "58") (name "unconnected-(IC3-B8-Pad12)") (class "Default")
      (node (ref "IC3") (pin "12") (pinfunction "B8_12") (pintype "bidirectional"))
    )
    (net (code "59") (name "unconnected-(JP1-Pad3)") (class "Default")
      (node (ref "JP1") (pin "3") (pinfunction "3_3") (pintype "passive"))
    )
    (net (code "60") (name "unconnected-(JP3-Pad2)") (class "Default")
      (node (ref "JP3") (pin "2") (pinfunction "2_2") (pintype "passive"))
    )
    (net (code "61") (name "unconnected-(JP3-Pad5)") (class "Default")
      (node (ref "JP3") (pin "5") (pinfunction "5_5") (pintype "passive"))
    )
    (net (code "62") (name "unconnected-(SOM1D-V+-PadJ1.24)") (class "Default")
      (node (ref "SOM1") (pin "J1.24") (pinfunction "V+_J1.24") (pintype "power_in"))
    )
    (net (code "63") (name "unconnected-(SOM1E-BATT_LINE-PadJ2.38)") (class "Default")
      (node (ref "SOM1") (pin "J2.38") (pinfunction "BATT_LINE_J2.38") (pintype "bidirectional"))
    )
    (net (code "64") (name "unconnected-(SOM1E-SYS_BOOT0{slash}LCD_D18-PadJ2.100)") (class "Default")
      (node (ref "SOM1") (pin "J2.100") (pinfunction "SYS_BOOT0/LCD_D18_J2.100") (pintype "bidirectional"))
    )
    (net (code "65") (name "unconnected-(SOM1E-SYS_BOOT5{slash}LCD_D22-PadJ2.89)") (class "Default")
      (node (ref "SOM1") (pin "J2.89") (pinfunction "SYS_BOOT5/LCD_D22_J2.89") (pintype "bidirectional"))
    )
    (net (code "66") (name "unconnected-(SOM1E-T2_REGEN-PadJ2.17)") (class "Default")
      (node (ref "SOM1") (pin "J2.17") (pinfunction "T2_REGEN_J2.17") (pintype "bidirectional"))
    )
    (net (code "67") (name "unconnected-(SOM1E-TWL_32K_CLK_OUT-PadJ2.15)") (class "Default")
      (node (ref "SOM1") (pin "J2.15") (pinfunction "TWL_32K_CLK_OUT_J2.15") (pintype "bidirectional"))
    )
    (net (code "68") (name "unconnected-(SOM1E-UP_CLKOUT1_26MHZ-PadJ2.88)") (class "Default")
      (node (ref "SOM1") (pin "J2.88") (pinfunction "UP_CLKOUT1_26MHZ_J2.88") (pintype "bidirectional"))
    )
    (net (code "69") (name "unconnected-(SOM1F-CAM_WEN-PadJ2.61)") (class "Default")
      (node (ref "SOM1") (pin "J2.61") (pinfunction "CAM_WEN_J2.61") (pintype "bidirectional"))
    )
    (net (code "70") (name "unconnected-(SOM1F-CSI_FLD-PadJ2.52)") (class "Default")
      (node (ref "SOM1") (pin "J2.52") (pinfunction "CSI_FLD_J2.52") (pintype "bidirectional"))
    )
    (net (code "71") (name "unconnected-(SOM1F-CSI_XCLKB-PadJ2.69)") (class "Default")
      (node (ref "SOM1") (pin "J2.69") (pinfunction "CSI_XCLKB_J2.69") (pintype "bidirectional"))
    )
    (net (code "72") (name "unconnected-(SOM1H-BT_PCM_DR-PadJ2.8)") (class "Default")
      (node (ref "SOM1") (pin "J2.8") (pinfunction "BT_PCM_DR_J2.8") (pintype "bidirectional"))
    )
    (net (code "73") (name "unconnected-(SOM1H-BT_PCM_DX-PadJ2.10)") (class "Default")
      (node (ref "SOM1") (pin "J2.10") (pinfunction "BT_PCM_DX_J2.10") (pintype "bidirectional"))
    )
    (net (code "74") (name "unconnected-(SOM1J-UP_I2C3_SCL-PadJ2.95)") (class "Default")
      (node (ref "SOM1") (pin "J2.95") (pinfunction "UP_I2C3_SCL_J2.95") (pintype "bidirectional"))
    )
    (net (code "75") (name "unconnected-(SOM1J-UP_I2C3_SDA-PadJ2.97)") (class "Default")
      (node (ref "SOM1") (pin "J2.97") (pinfunction "UP_I2C3_SDA_J2.97") (pintype "bidirectional"))
    )
    (net (code "76") (name "unconnected-(SOM1O-SD2_CLK-PadJ1.89)") (class "Default")
      (node (ref "SOM1") (pin "J1.89") (pinfunction "SD2_CLK_J1.89") (pintype "bidirectional"))
    )
    (net (code "77") (name "unconnected-(SOM1O-SD2_CMD-PadJ1.97)") (class "Default")
      (node (ref "SOM1") (pin "J1.97") (pinfunction "SD2_CMD_J1.97") (pintype "bidirectional"))
    )
    (net (code "78") (name "unconnected-(SOM1O-SD2_DATA0-PadJ1.84)") (class "Default")
      (node (ref "SOM1") (pin "J1.84") (pinfunction "SD2_DATA0_J1.84") (pintype "bidirectional"))
    )
    (net (code "79") (name "unconnected-(SOM1O-SD2_DATA1-PadJ1.95)") (class "Default")
      (node (ref "SOM1") (pin "J1.95") (pinfunction "SD2_DATA1_J1.95") (pintype "bidirectional"))
    )
    (net (code "80") (name "unconnected-(SOM1O-SD2_DATA2-PadJ1.93)") (class "Default")
      (node (ref "SOM1") (pin "J1.93") (pinfunction "SD2_DATA2_J1.93") (pintype "bidirectional"))
    )
    (net (code "81") (name "unconnected-(SOM1O-SD2_DATA3-PadJ1.91)") (class "Default")
      (node (ref "SOM1") (pin "J1.91") (pinfunction "SD2_DATA3_J1.91") (pintype "bidirectional"))
    )
    (net (code "82") (name "unconnected-(SOM1O-SD3_DATA0-PadJ1.96)") (class "Default")
      (node (ref "SOM1") (pin "J1.96") (pinfunction "SD3_DATA0_J1.96") (pintype "bidirectional"))
    )
    (net (code "83") (name "unconnected-(SOM1O-SD3_DATA1-PadJ1.94)") (class "Default")
      (node (ref "SOM1") (pin "J1.94") (pinfunction "SD3_DATA1_J1.94") (pintype "bidirectional"))
    )
    (net (code "84") (name "unconnected-(SOM1O-SD3_DATA2-PadJ1.92)") (class "Default")
      (node (ref "SOM1") (pin "J1.92") (pinfunction "SD3_DATA2_J1.92") (pintype "bidirectional"))
    )
    (net (code "85") (name "unconnected-(SOM1O-SD3_DATA3-PadJ1.90)") (class "Default")
      (node (ref "SOM1") (pin "J1.90") (pinfunction "SD3_DATA3_J1.90") (pintype "bidirectional"))
    )
    (net (code "86") (name "unconnected-(SOM1P-UP_UARTB_CTS-PadJ2.37)") (class "Default")
      (node (ref "SOM1") (pin "J2.37") (pinfunction "UP_UARTB_CTS_J2.37") (pintype "bidirectional"))
    )
    (net (code "87") (name "unconnected-(SOM1P-UP_UARTB_RTS-PadJ2.39)") (class "Default")
      (node (ref "SOM1") (pin "J2.39") (pinfunction "UP_UARTB_RTS_J2.39") (pintype "bidirectional"))
    )
    (net (code "88") (name "unconnected-(SOM1P-UP_UARTC_CTS-PadJ2.76)") (class "Default")
      (node (ref "SOM1") (pin "J2.76") (pinfunction "UP_UARTC_CTS_J2.76") (pintype "bidirectional"))
    )
    (net (code "89") (name "unconnected-(SOM1P-UP_UARTC_RTS-PadJ2.74)") (class "Default")
      (node (ref "SOM1") (pin "J2.74") (pinfunction "UP_UARTC_RTS_J2.74") (pintype "bidirectional"))
    )
    (net (code "90") (name "unconnected-(SOM1P-UP_UARTC_RX-PadJ2.86)") (class "Default")
      (node (ref "SOM1") (pin "J2.86") (pinfunction "UP_UARTC_RX_J2.86") (pintype "bidirectional"))
    )
    (net (code "91") (name "unconnected-(SOM1P-UP_UARTC_TX-PadJ2.72)") (class "Default")
      (node (ref "SOM1") (pin "J2.72") (pinfunction "UP_UARTC_TX_J2.72") (pintype "bidirectional"))
    )
    (net (code "92") (name "unconnected-(SOM1Q-USB1_ID-PadJ2.9)") (class "Default")
      (node (ref "SOM1") (pin "J2.9") (pinfunction "USB1_ID_J2.9") (pintype "bidirectional"))
    )
    (net (code "93") (name "~{RESET}") (class "Default")
      (node (ref "CAM1") (pin "20") (pinfunction "~{RESET}_20") (pintype "input"))
      (node (ref "CAM2") (pin "6") (pinfunction "~{RESET}_6") (pintype "input"))
      (node (ref "SOM1") (pin "J2.6") (pinfunction "SYS_NRESWARM_J2.6") (pintype "bidirectional"))
    )
  )
)
